# Battery.net
KiCad netlist of a schematic drawn in EAGLE
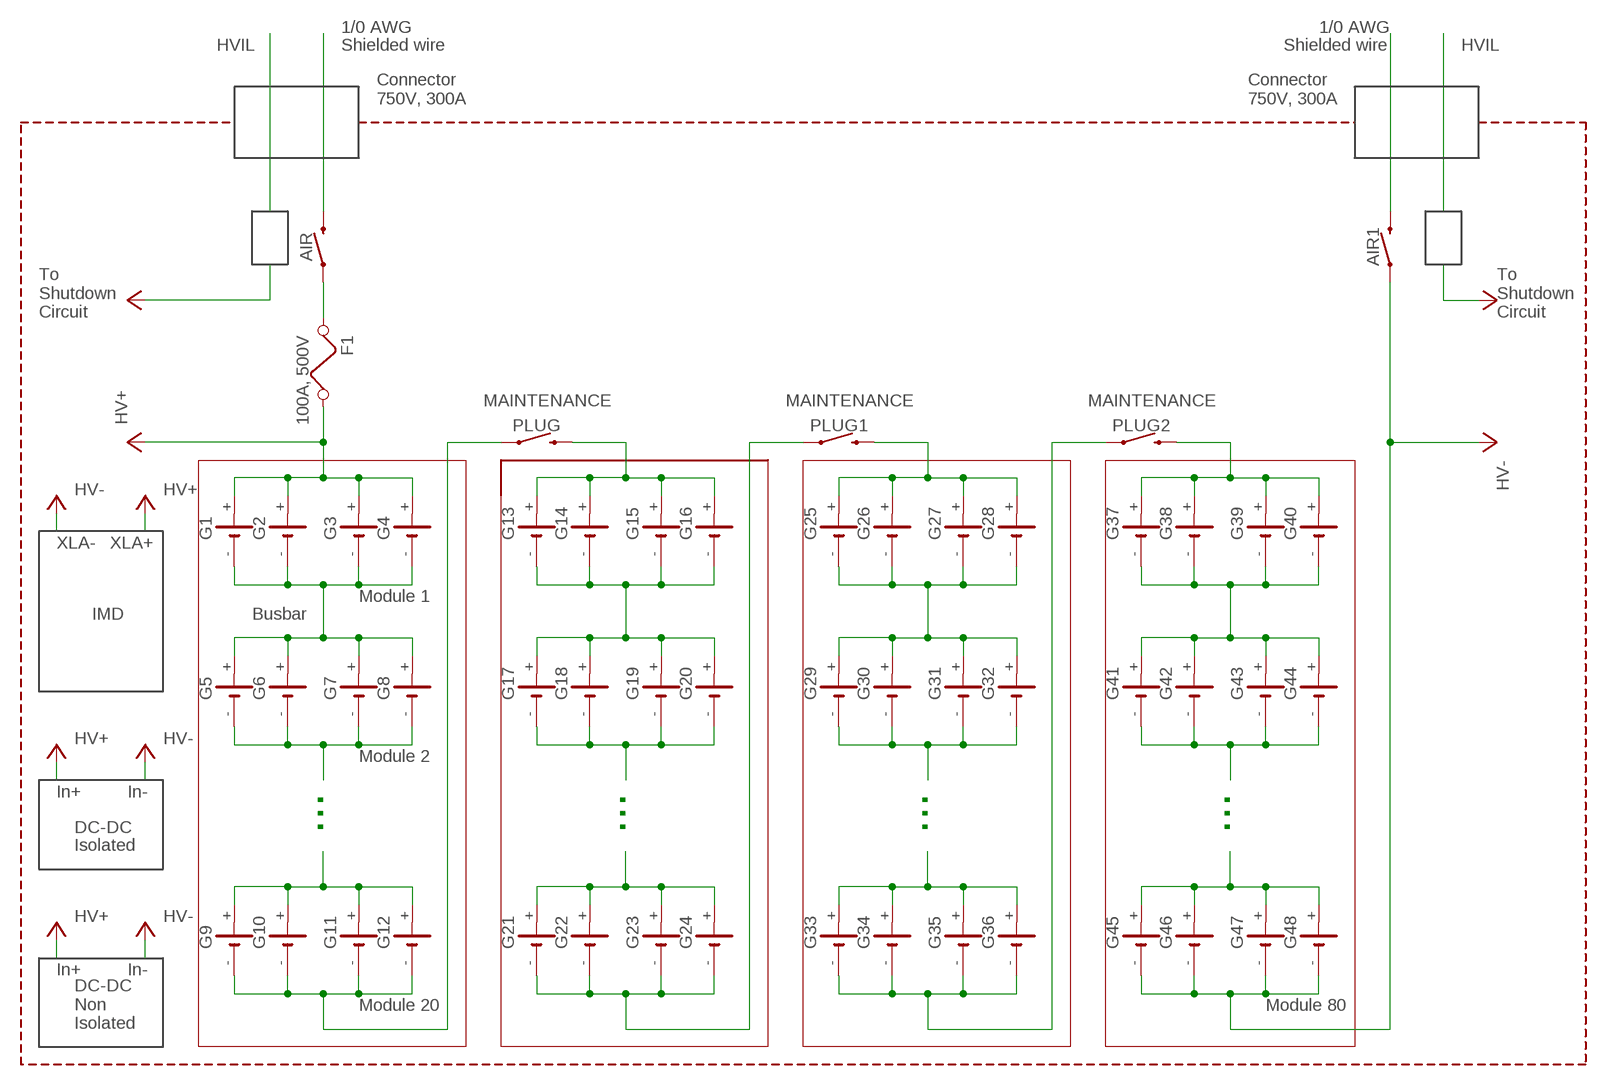
[diagram p0: schematic, sheet 1]

(export (version "E")
  (design (tool "Eeschema 10.0.6"))
  (components
    (comp (ref "AIR")
      (value "MOMENTARY-SWITCH-SPST-PTH-6.0MM")
      (footprint "eagle-import:TACTILE_SWITCH_PTH_6.0MM")
      (libsource (lib "eagle-import") (part "MOMENTARY-SWITCH-SPST-PTH-6.0MM"))
    )
    (comp (ref "AIR1")
      (value "MOMENTARY-SWITCH-SPST-PTH-6.0MM")
      (footprint "eagle-import:TACTILE_SWITCH_PTH_6.0MM")
      (libsource (lib "eagle-import") (part "MOMENTARY-SWITCH-SPST-PTH-6.0MM"))
    )
    (comp (ref "F1")
      (value "100A, 500V")
      (footprint "eagle-import:FUSE")
      (libsource (lib "eagle-import") (part "FUSE"))
    )
    (comp (ref "G1")
      (value "SL-160AA/PR")
      (footprint "eagle-import:SL-160AA_PR")
      (libsource (lib "eagle-import") (part "SL-160AA/PR"))
    )
    (comp (ref "G2")
      (value "SL-160AA/PR")
      (footprint "eagle-import:SL-160AA_PR")
      (libsource (lib "eagle-import") (part "SL-160AA/PR"))
    )
    (comp (ref "G3")
      (value "SL-160AA/PR")
      (footprint "eagle-import:SL-160AA_PR")
      (libsource (lib "eagle-import") (part "SL-160AA/PR"))
    )
    (comp (ref "G4")
      (value "SL-160AA/PR")
      (footprint "eagle-import:SL-160AA_PR")
      (libsource (lib "eagle-import") (part "SL-160AA/PR"))
    )
    (comp (ref "G5")
      (value "SL-160AA/PR")
      (footprint "eagle-import:SL-160AA_PR")
      (libsource (lib "eagle-import") (part "SL-160AA/PR"))
    )
    (comp (ref "G6")
      (value "SL-160AA/PR")
      (footprint "eagle-import:SL-160AA_PR")
      (libsource (lib "eagle-import") (part "SL-160AA/PR"))
    )
    (comp (ref "G7")
      (value "SL-160AA/PR")
      (footprint "eagle-import:SL-160AA_PR")
      (libsource (lib "eagle-import") (part "SL-160AA/PR"))
    )
    (comp (ref "G8")
      (value "SL-160AA/PR")
      (footprint "eagle-import:SL-160AA_PR")
      (libsource (lib "eagle-import") (part "SL-160AA/PR"))
    )
    (comp (ref "G9")
      (value "SL-160AA/PR")
      (footprint "eagle-import:SL-160AA_PR")
      (libsource (lib "eagle-import") (part "SL-160AA/PR"))
    )
    (comp (ref "G10")
      (value "SL-160AA/PR")
      (footprint "eagle-import:SL-160AA_PR")
      (libsource (lib "eagle-import") (part "SL-160AA/PR"))
    )
    (comp (ref "G11")
      (value "SL-160AA/PR")
      (footprint "eagle-import:SL-160AA_PR")
      (libsource (lib "eagle-import") (part "SL-160AA/PR"))
    )
    (comp (ref "G12")
      (value "SL-160AA/PR")
      (footprint "eagle-import:SL-160AA_PR")
      (libsource (lib "eagle-import") (part "SL-160AA/PR"))
    )
    (comp (ref "G13")
      (value "SL-160AA/PR")
      (footprint "eagle-import:SL-160AA_PR")
      (libsource (lib "eagle-import") (part "SL-160AA/PR"))
    )
    (comp (ref "G14")
      (value "SL-160AA/PR")
      (footprint "eagle-import:SL-160AA_PR")
      (libsource (lib "eagle-import") (part "SL-160AA/PR"))
    )
    (comp (ref "G15")
      (value "SL-160AA/PR")
      (footprint "eagle-import:SL-160AA_PR")
      (libsource (lib "eagle-import") (part "SL-160AA/PR"))
    )
    (comp (ref "G16")
      (value "SL-160AA/PR")
      (footprint "eagle-import:SL-160AA_PR")
      (libsource (lib "eagle-import") (part "SL-160AA/PR"))
    )
    (comp (ref "G17")
      (value "SL-160AA/PR")
      (footprint "eagle-import:SL-160AA_PR")
      (libsource (lib "eagle-import") (part "SL-160AA/PR"))
    )
    (comp (ref "G18")
      (value "SL-160AA/PR")
      (footprint "eagle-import:SL-160AA_PR")
      (libsource (lib "eagle-import") (part "SL-160AA/PR"))
    )
    (comp (ref "G19")
      (value "SL-160AA/PR")
      (footprint "eagle-import:SL-160AA_PR")
      (libsource (lib "eagle-import") (part "SL-160AA/PR"))
    )
    (comp (ref "G20")
      (value "SL-160AA/PR")
      (footprint "eagle-import:SL-160AA_PR")
      (libsource (lib "eagle-import") (part "SL-160AA/PR"))
    )
    (comp (ref "G21")
      (value "SL-160AA/PR")
      (footprint "eagle-import:SL-160AA_PR")
      (libsource (lib "eagle-import") (part "SL-160AA/PR"))
    )
    (comp (ref "G22")
      (value "SL-160AA/PR")
      (footprint "eagle-import:SL-160AA_PR")
      (libsource (lib "eagle-import") (part "SL-160AA/PR"))
    )
    (comp (ref "G23")
      (value "SL-160AA/PR")
      (footprint "eagle-import:SL-160AA_PR")
      (libsource (lib "eagle-import") (part "SL-160AA/PR"))
    )
    (comp (ref "G24")
      (value "SL-160AA/PR")
      (footprint "eagle-import:SL-160AA_PR")
      (libsource (lib "eagle-import") (part "SL-160AA/PR"))
    )
    (comp (ref "G25")
      (value "SL-160AA/PR")
      (footprint "eagle-import:SL-160AA_PR")
      (libsource (lib "eagle-import") (part "SL-160AA/PR"))
    )
    (comp (ref "G26")
      (value "SL-160AA/PR")
      (footprint "eagle-import:SL-160AA_PR")
      (libsource (lib "eagle-import") (part "SL-160AA/PR"))
    )
    (comp (ref "G27")
      (value "SL-160AA/PR")
      (footprint "eagle-import:SL-160AA_PR")
      (libsource (lib "eagle-import") (part "SL-160AA/PR"))
    )
    (comp (ref "G28")
      (value "SL-160AA/PR")
      (footprint "eagle-import:SL-160AA_PR")
      (libsource (lib "eagle-import") (part "SL-160AA/PR"))
    )
    (comp (ref "G29")
      (value "SL-160AA/PR")
      (footprint "eagle-import:SL-160AA_PR")
      (libsource (lib "eagle-import") (part "SL-160AA/PR"))
    )
    (comp (ref "G30")
      (value "SL-160AA/PR")
      (footprint "eagle-import:SL-160AA_PR")
      (libsource (lib "eagle-import") (part "SL-160AA/PR"))
    )
    (comp (ref "G31")
      (value "SL-160AA/PR")
      (footprint "eagle-import:SL-160AA_PR")
      (libsource (lib "eagle-import") (part "SL-160AA/PR"))
    )
    (comp (ref "G32")
      (value "SL-160AA/PR")
      (footprint "eagle-import:SL-160AA_PR")
      (libsource (lib "eagle-import") (part "SL-160AA/PR"))
    )
    (comp (ref "G33")
      (value "SL-160AA/PR")
      (footprint "eagle-import:SL-160AA_PR")
      (libsource (lib "eagle-import") (part "SL-160AA/PR"))
    )
    (comp (ref "G34")
      (value "SL-160AA/PR")
      (footprint "eagle-import:SL-160AA_PR")
      (libsource (lib "eagle-import") (part "SL-160AA/PR"))
    )
    (comp (ref "G35")
      (value "SL-160AA/PR")
      (footprint "eagle-import:SL-160AA_PR")
      (libsource (lib "eagle-import") (part "SL-160AA/PR"))
    )
    (comp (ref "G36")
      (value "SL-160AA/PR")
      (footprint "eagle-import:SL-160AA_PR")
      (libsource (lib "eagle-import") (part "SL-160AA/PR"))
    )
    (comp (ref "G37")
      (value "SL-160AA/PR")
      (footprint "eagle-import:SL-160AA_PR")
      (libsource (lib "eagle-import") (part "SL-160AA/PR"))
    )
    (comp (ref "G38")
      (value "SL-160AA/PR")
      (footprint "eagle-import:SL-160AA_PR")
      (libsource (lib "eagle-import") (part "SL-160AA/PR"))
    )
    (comp (ref "G39")
      (value "SL-160AA/PR")
      (footprint "eagle-import:SL-160AA_PR")
      (libsource (lib "eagle-import") (part "SL-160AA/PR"))
    )
    (comp (ref "G40")
      (value "SL-160AA/PR")
      (footprint "eagle-import:SL-160AA_PR")
      (libsource (lib "eagle-import") (part "SL-160AA/PR"))
    )
    (comp (ref "G41")
      (value "SL-160AA/PR")
      (footprint "eagle-import:SL-160AA_PR")
      (libsource (lib "eagle-import") (part "SL-160AA/PR"))
    )
    (comp (ref "G42")
      (value "SL-160AA/PR")
      (footprint "eagle-import:SL-160AA_PR")
      (libsource (lib "eagle-import") (part "SL-160AA/PR"))
    )
    (comp (ref "G43")
      (value "SL-160AA/PR")
      (footprint "eagle-import:SL-160AA_PR")
      (libsource (lib "eagle-import") (part "SL-160AA/PR"))
    )
    (comp (ref "G44")
      (value "SL-160AA/PR")
      (footprint "eagle-import:SL-160AA_PR")
      (libsource (lib "eagle-import") (part "SL-160AA/PR"))
    )
    (comp (ref "G45")
      (value "SL-160AA/PR")
      (footprint "eagle-import:SL-160AA_PR")
      (libsource (lib "eagle-import") (part "SL-160AA/PR"))
    )
    (comp (ref "G46")
      (value "SL-160AA/PR")
      (footprint "eagle-import:SL-160AA_PR")
      (libsource (lib "eagle-import") (part "SL-160AA/PR"))
    )
    (comp (ref "G47")
      (value "SL-160AA/PR")
      (footprint "eagle-import:SL-160AA_PR")
      (libsource (lib "eagle-import") (part "SL-160AA/PR"))
    )
    (comp (ref "G48")
      (value "SL-160AA/PR")
      (footprint "eagle-import:SL-160AA_PR")
      (libsource (lib "eagle-import") (part "SL-160AA/PR"))
    )
    (comp (ref "PLUG")
      (value "MOMENTARY-SWITCH-SPST-PTH-6.0MM")
      (footprint "eagle-import:TACTILE_SWITCH_PTH_6.0MM")
      (libsource (lib "eagle-import") (part "MOMENTARY-SWITCH-SPST-PTH-6.0MM"))
    )
    (comp (ref "PLUG1")
      (value "MOMENTARY-SWITCH-SPST-PTH-6.0MM")
      (footprint "eagle-import:TACTILE_SWITCH_PTH_6.0MM")
      (libsource (lib "eagle-import") (part "MOMENTARY-SWITCH-SPST-PTH-6.0MM"))
    )
    (comp (ref "PLUG2")
      (value "MOMENTARY-SWITCH-SPST-PTH-6.0MM")
      (footprint "eagle-import:TACTILE_SWITCH_PTH_6.0MM")
      (libsource (lib "eagle-import") (part "MOMENTARY-SWITCH-SPST-PTH-6.0MM"))
    )
  )
  (nets
    (net (code "1") (name "+5V") (class "Default")
      (node (ref "AIR1") (pin "1") (pinfunction "1_1") (pintype "passive"))
      (node (ref "F1") (pin "2") (pinfunction "2_2") (pintype "passive"))
      (node (ref "G1") (pin "+") (pinfunction "+_+") (pintype "passive"))
      (node (ref "G2") (pin "+") (pinfunction "+_+") (pintype "passive"))
      (node (ref "G3") (pin "+") (pinfunction "+_+") (pintype "passive"))
      (node (ref "G4") (pin "+") (pinfunction "+_+") (pintype "passive"))
      (node (ref "G45") (pin "-") (pinfunction "-_-") (pintype "passive"))
      (node (ref "G46") (pin "-") (pinfunction "-_-") (pintype "passive"))
      (node (ref "G47") (pin "-") (pinfunction "-_-") (pintype "passive"))
      (node (ref "G48") (pin "-") (pinfunction "-_-") (pintype "passive"))
    )
    (net (code "2") (name "Net-(AIR-Pad1)") (class "Default")
      (node (ref "AIR") (pin "1") (pinfunction "1_1") (pintype "passive"))
      (node (ref "F1") (pin "1") (pinfunction "1_1") (pintype "passive"))
    )
    (net (code "3") (name "Net-(G1-Pad-)") (class "Default")
      (node (ref "G1") (pin "-") (pinfunction "-_-") (pintype "passive"))
      (node (ref "G2") (pin "-") (pinfunction "-_-") (pintype "passive"))
      (node (ref "G3") (pin "-") (pinfunction "-_-") (pintype "passive"))
      (node (ref "G4") (pin "-") (pinfunction "-_-") (pintype "passive"))
      (node (ref "G5") (pin "+") (pinfunction "+_+") (pintype "passive"))
      (node (ref "G6") (pin "+") (pinfunction "+_+") (pintype "passive"))
      (node (ref "G7") (pin "+") (pinfunction "+_+") (pintype "passive"))
      (node (ref "G8") (pin "+") (pinfunction "+_+") (pintype "passive"))
    )
    (net (code "4") (name "Net-(G5-Pad-)") (class "Default")
      (node (ref "G5") (pin "-") (pinfunction "-_-") (pintype "passive"))
      (node (ref "G6") (pin "-") (pinfunction "-_-") (pintype "passive"))
      (node (ref "G7") (pin "-") (pinfunction "-_-") (pintype "passive"))
      (node (ref "G8") (pin "-") (pinfunction "-_-") (pintype "passive"))
    )
    (net (code "5") (name "Net-(G10-Pad+)") (class "Default")
      (node (ref "G10") (pin "+") (pinfunction "+_+") (pintype "passive"))
      (node (ref "G11") (pin "+") (pinfunction "+_+") (pintype "passive"))
      (node (ref "G12") (pin "+") (pinfunction "+_+") (pintype "passive"))
      (node (ref "G9") (pin "+") (pinfunction "+_+") (pintype "passive"))
    )
    (net (code "6") (name "Net-(G10-Pad-)") (class "Default")
      (node (ref "G10") (pin "-") (pinfunction "-_-") (pintype "passive"))
      (node (ref "G11") (pin "-") (pinfunction "-_-") (pintype "passive"))
      (node (ref "G12") (pin "-") (pinfunction "-_-") (pintype "passive"))
      (node (ref "G9") (pin "-") (pinfunction "-_-") (pintype "passive"))
      (node (ref "PLUG") (pin "1") (pinfunction "1_1") (pintype "passive"))
    )
    (net (code "7") (name "Net-(G13-Pad-)") (class "Default")
      (node (ref "G13") (pin "-") (pinfunction "-_-") (pintype "passive"))
      (node (ref "G14") (pin "-") (pinfunction "-_-") (pintype "passive"))
      (node (ref "G15") (pin "-") (pinfunction "-_-") (pintype "passive"))
      (node (ref "G16") (pin "-") (pinfunction "-_-") (pintype "passive"))
      (node (ref "G17") (pin "+") (pinfunction "+_+") (pintype "passive"))
      (node (ref "G18") (pin "+") (pinfunction "+_+") (pintype "passive"))
      (node (ref "G19") (pin "+") (pinfunction "+_+") (pintype "passive"))
      (node (ref "G20") (pin "+") (pinfunction "+_+") (pintype "passive"))
    )
    (net (code "8") (name "Net-(G17-Pad-)") (class "Default")
      (node (ref "G17") (pin "-") (pinfunction "-_-") (pintype "passive"))
      (node (ref "G18") (pin "-") (pinfunction "-_-") (pintype "passive"))
      (node (ref "G19") (pin "-") (pinfunction "-_-") (pintype "passive"))
      (node (ref "G20") (pin "-") (pinfunction "-_-") (pintype "passive"))
    )
    (net (code "9") (name "Net-(G21-Pad+)") (class "Default")
      (node (ref "G21") (pin "+") (pinfunction "+_+") (pintype "passive"))
      (node (ref "G22") (pin "+") (pinfunction "+_+") (pintype "passive"))
      (node (ref "G23") (pin "+") (pinfunction "+_+") (pintype "passive"))
      (node (ref "G24") (pin "+") (pinfunction "+_+") (pintype "passive"))
    )
    (net (code "10") (name "Net-(G21-Pad-)") (class "Default")
      (node (ref "G21") (pin "-") (pinfunction "-_-") (pintype "passive"))
      (node (ref "G22") (pin "-") (pinfunction "-_-") (pintype "passive"))
      (node (ref "G23") (pin "-") (pinfunction "-_-") (pintype "passive"))
      (node (ref "G24") (pin "-") (pinfunction "-_-") (pintype "passive"))
      (node (ref "PLUG1") (pin "1") (pinfunction "1_1") (pintype "passive"))
    )
    (net (code "11") (name "Net-(G25-Pad-)") (class "Default")
      (node (ref "G25") (pin "-") (pinfunction "-_-") (pintype "passive"))
      (node (ref "G26") (pin "-") (pinfunction "-_-") (pintype "passive"))
      (node (ref "G27") (pin "-") (pinfunction "-_-") (pintype "passive"))
      (node (ref "G28") (pin "-") (pinfunction "-_-") (pintype "passive"))
      (node (ref "G29") (pin "+") (pinfunction "+_+") (pintype "passive"))
      (node (ref "G30") (pin "+") (pinfunction "+_+") (pintype "passive"))
      (node (ref "G31") (pin "+") (pinfunction "+_+") (pintype "passive"))
      (node (ref "G32") (pin "+") (pinfunction "+_+") (pintype "passive"))
    )
    (net (code "12") (name "Net-(G29-Pad-)") (class "Default")
      (node (ref "G29") (pin "-") (pinfunction "-_-") (pintype "passive"))
      (node (ref "G30") (pin "-") (pinfunction "-_-") (pintype "passive"))
      (node (ref "G31") (pin "-") (pinfunction "-_-") (pintype "passive"))
      (node (ref "G32") (pin "-") (pinfunction "-_-") (pintype "passive"))
    )
    (net (code "13") (name "Net-(G33-Pad+)") (class "Default")
      (node (ref "G33") (pin "+") (pinfunction "+_+") (pintype "passive"))
      (node (ref "G34") (pin "+") (pinfunction "+_+") (pintype "passive"))
      (node (ref "G35") (pin "+") (pinfunction "+_+") (pintype "passive"))
      (node (ref "G36") (pin "+") (pinfunction "+_+") (pintype "passive"))
    )
    (net (code "14") (name "Net-(G33-Pad-)") (class "Default")
      (node (ref "G33") (pin "-") (pinfunction "-_-") (pintype "passive"))
      (node (ref "G34") (pin "-") (pinfunction "-_-") (pintype "passive"))
      (node (ref "G35") (pin "-") (pinfunction "-_-") (pintype "passive"))
      (node (ref "G36") (pin "-") (pinfunction "-_-") (pintype "passive"))
      (node (ref "PLUG2") (pin "1") (pinfunction "1_1") (pintype "passive"))
    )
    (net (code "15") (name "Net-(G37-Pad-)") (class "Default")
      (node (ref "G37") (pin "-") (pinfunction "-_-") (pintype "passive"))
      (node (ref "G38") (pin "-") (pinfunction "-_-") (pintype "passive"))
      (node (ref "G39") (pin "-") (pinfunction "-_-") (pintype "passive"))
      (node (ref "G40") (pin "-") (pinfunction "-_-") (pintype "passive"))
      (node (ref "G41") (pin "+") (pinfunction "+_+") (pintype "passive"))
      (node (ref "G42") (pin "+") (pinfunction "+_+") (pintype "passive"))
      (node (ref "G43") (pin "+") (pinfunction "+_+") (pintype "passive"))
      (node (ref "G44") (pin "+") (pinfunction "+_+") (pintype "passive"))
    )
    (net (code "16") (name "Net-(G41-Pad-)") (class "Default")
      (node (ref "G41") (pin "-") (pinfunction "-_-") (pintype "passive"))
      (node (ref "G42") (pin "-") (pinfunction "-_-") (pintype "passive"))
      (node (ref "G43") (pin "-") (pinfunction "-_-") (pintype "passive"))
      (node (ref "G44") (pin "-") (pinfunction "-_-") (pintype "passive"))
    )
    (net (code "17") (name "Net-(G45-Pad+)") (class "Default")
      (node (ref "G45") (pin "+") (pinfunction "+_+") (pintype "passive"))
      (node (ref "G46") (pin "+") (pinfunction "+_+") (pintype "passive"))
      (node (ref "G47") (pin "+") (pinfunction "+_+") (pintype "passive"))
      (node (ref "G48") (pin "+") (pinfunction "+_+") (pintype "passive"))
    )
    (net (code "18") (name "Net-(PLUG-2)") (class "Default")
      (node (ref "G13") (pin "+") (pinfunction "+_+") (pintype "passive"))
      (node (ref "G14") (pin "+") (pinfunction "+_+") (pintype "passive"))
      (node (ref "G15") (pin "+") (pinfunction "+_+") (pintype "passive"))
      (node (ref "G16") (pin "+") (pinfunction "+_+") (pintype "passive"))
      (node (ref "PLUG") (pin "3") (pinfunction "2_3") (pintype "passive"))
    )
    (net (code "19") (name "Net-(PLUG1-2)") (class "Default")
      (node (ref "G25") (pin "+") (pinfunction "+_+") (pintype "passive"))
      (node (ref "G26") (pin "+") (pinfunction "+_+") (pintype "passive"))
      (node (ref "G27") (pin "+") (pinfunction "+_+") (pintype "passive"))
      (node (ref "G28") (pin "+") (pinfunction "+_+") (pintype "passive"))
      (node (ref "PLUG1") (pin "3") (pinfunction "2_3") (pintype "passive"))
    )
    (net (code "20") (name "Net-(PLUG2-2)") (class "Default")
      (node (ref "G37") (pin "+") (pinfunction "+_+") (pintype "passive"))
      (node (ref "G38") (pin "+") (pinfunction "+_+") (pintype "passive"))
      (node (ref "G39") (pin "+") (pinfunction "+_+") (pintype "passive"))
      (node (ref "G40") (pin "+") (pinfunction "+_+") (pintype "passive"))
      (node (ref "PLUG2") (pin "3") (pinfunction "2_3") (pintype "passive"))
    )
    (net (code "21") (name "unconnected-(AIR-2-Pad3)") (class "Default")
      (node (ref "AIR") (pin "3") (pinfunction "2_3") (pintype "passive"))
    )
    (net (code "22") (name "unconnected-(AIR1-2-Pad3)") (class "Default")
      (node (ref "AIR1") (pin "3") (pinfunction "2_3") (pintype "passive"))
    )
  )
)
